# InputFilter.net
KiCad netlist of a schematic drawn in Altium Designer
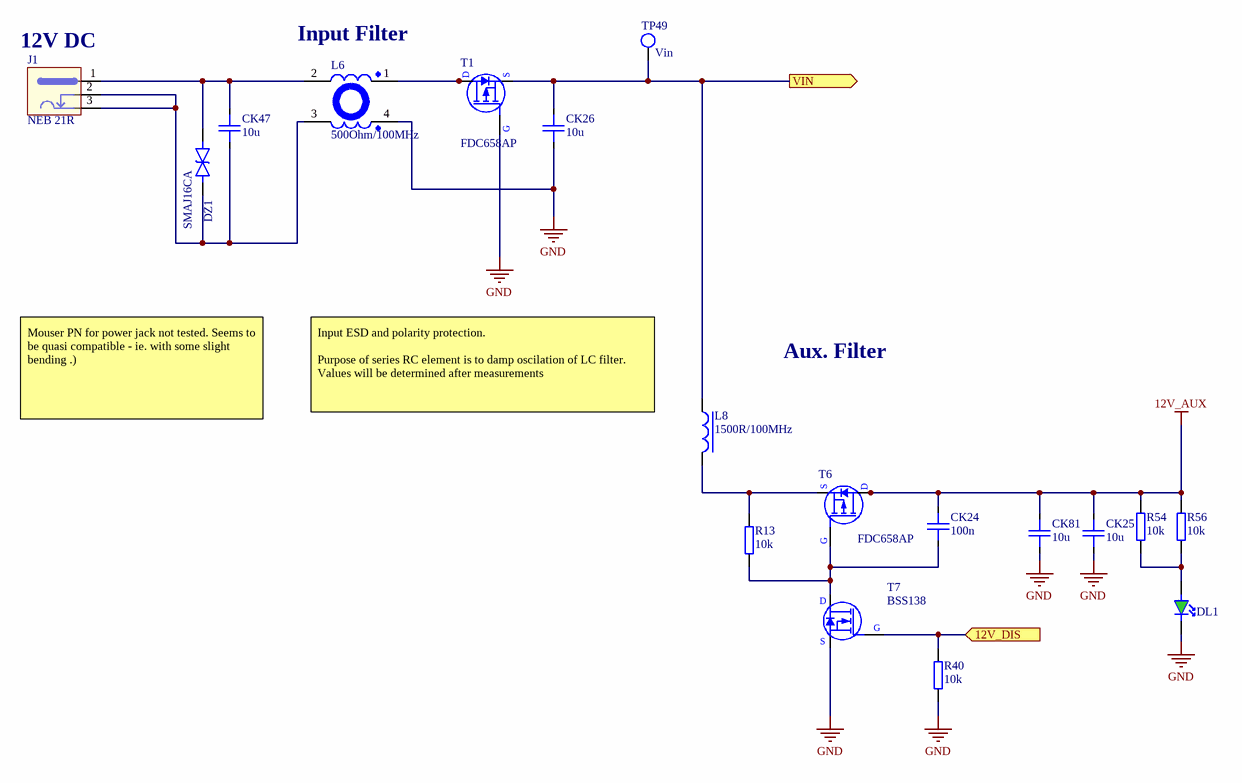
[diagram p0: InputFilter.SchDoc]

(export (version "E")
  (design (tool "Eeschema 10.0.6"))
  (components
    (comp (ref "CK24")
      (value "100n")
      (footprint "CAPC1608X09N(SMC0603)")
      (description "MLCC")
      (fields
        (field (name "TOLERANCE") "10%")
        (field (name "VOLTAGE") "50V")
        (field (name "AUTHOR") "JP/27.03.2014")
      )
      (libsource (lib "JP_C") (part "100n-50V-0603-X7R"))
    )
    (comp (ref "CK25")
      (value "10u")
      (footprint "CAPC3216X12N(SMC1206)")
      (description "MLCC")
      (fields
        (field (name "TOLERANCE") "10%")
        (field (name "VOLTAGE") "50")
        (field (name "AUTHOR") "JP/10.06.2014")
      )
      (libsource (lib "JP_C") (part "10u-50V-1206-X5R"))
    )
    (comp (ref "CK26")
      (value "10u")
      (footprint "CAPC3216X12N(SMC1206)")
      (description "MLCC")
      (fields
        (field (name "VOLTAGE") "50")
        (field (name "TOLERANCE") "10%")
        (field (name "AUTHOR") "JP/10.06.2014")
      )
      (libsource (lib "JP_C") (part "10u-50V-1206-X5R"))
    )
    (comp (ref "CK47")
      (value "10u")
      (footprint "CAPC3216X12N(SMC1206)")
      (description "MLCC")
      (fields
        (field (name "TOLERANCE") "10%")
        (field (name "VOLTAGE") "50")
        (field (name "AUTHOR") "JP/10.06.2014")
      )
      (libsource (lib "JP_C") (part "10u-50V-1206-X5R"))
    )
    (comp (ref "CK81")
      (value "10u")
      (footprint "CAPC3216X12N(SMC1206)")
      (description "MLCC")
      (fields
        (field (name "TOLERANCE") "10%")
        (field (name "VOLTAGE") "50")
        (field (name "AUTHOR") "JP/10.06.2014")
      )
      (libsource (lib "JP_C") (part "10u-50V-1206-X5R"))
    )
    (comp (ref "DL1")
      (value "GREEN")
      (footprint "0603diode")
      (description "Green LED, 0603")
      (fields (field (name "AUTHOR") "JP/31.3.2014"))
      (libsource (lib "IC") (part "LED_GREEN_0603"))
    )
    (comp (ref "DZ1")
      (value "SMAJ16CA")
      (footprint "DIOM5127X23N(SMA)")
      (description "Surface Mount TRANSZORB TVS, 16V StandOff, 400W, SMA")
      (libsource (lib "JP_IC") (part "SMAJ16CA"))
    )
    (comp (ref "J1")
      (value "NEB 21R")
      (footprint "NEB 21 R")
      (description "Power Jack Socket 1.95/6mm")
      (libsource (lib "JP_CONN") (part "Lumberg NEB 21 R"))
    )
    (comp (ref "L6")
      (value "500Ohm/100MHz")
      (footprint "DLW5BT")
      (description "CHOKE, COMMON, 4A, 500OHM, 100MHZ")
      (fields (field (name "AUTHOR") "JP 15.10.2014"))
      (libsource (lib "BTL_L") (part "EL+EMICHOKE4A"))
    )
    (comp (ref "L8")
      (value "1500R/100MHz")
      (footprint "INDC2012X08N(SML0805)")
      (description "Multilayer SMD Ferrite 1500R/100MHz")
      (fields (field (name "AUTHOR") "JP/05.06.2014"))
      (libsource (lib "JP_L") (part "MMZ2012Y152B"))
    )
    (comp (ref "R13")
      (value "10k")
      (footprint "RESC1608X06N(SMR0603)")
      (description "Chip Resistor")
      (fields (field (name "AUTHOR") "JP/10.06.2014"))
      (libsource (lib "JP_R") (part "10k-100mW-0603-ThickFilm"))
    )
    (comp (ref "R40")
      (value "10k")
      (footprint "RESC1608X06N(SMR0603)")
      (description "Chip Resistor")
      (fields (field (name "AUTHOR") "JP/10.06.2014"))
      (libsource (lib "JP_R") (part "10k-100mW-0603-ThickFilm"))
    )
    (comp (ref "R54")
      (value "10k")
      (footprint "RESC1608X06N(SMR0603)")
      (description "Chip Resistor")
      (fields (field (name "AUTHOR") "JP/10.06.2014"))
      (libsource (lib "JP_R") (part "10k-100mW-0603-ThickFilm"))
    )
    (comp (ref "R56")
      (value "10k")
      (footprint "RESC1608X06N(SMR0603)")
      (description "Chip Resistor")
      (fields (field (name "AUTHOR") "JP/10.06.2014"))
      (libsource (lib "JP_R") (part "10k-100mW-0603-ThickFilm"))
    )
    (comp (ref "T1")
      (value "FDC658AP")
      (footprint "TSOP95P280X110-6N(SuperSOT6)")
      (description "30V P  -  Channel PowerTrench  MOSFET")
      (libsource (lib "JP_IC") (part "FDC658AP"))
    )
    (comp (ref "T6")
      (value "FDC658AP")
      (footprint "TSOP95P280X110-6N(SuperSOT6)")
      (description "30V P  -  Channel PowerTrench  MOSFET")
      (libsource (lib "JP_IC") (part "FDC658AP"))
    )
    (comp (ref "T7")
      (value "BSS138")
      (footprint "SOT95P230X110-3N(SOT23)")
      (description "N-MOSFET, Logic Level, 50V/0,22A/3.5Ohm")
      (fields (field (name "AUTHOR") "JM 2.7.2014"))
      (libsource (lib "JP_IC") (part "ET+BSS138XX0"))
    )
    (comp (ref "TP49")
      (value "Vin")
      (footprint "TP_0.8/0.4_ROUND")
      (description "Testpoint - VIA")
      (libsource (lib "JP_CONN") (part "TEST_POINT_VIA"))
    )
  )
  (nets
    (net (code "1") (name "/12V_DIS") (class "Default")
      (node (ref "R40") (pin "2") (pinfunction "2_2") (pintype "passive"))
      (node (ref "T7") (pin "1") (pinfunction "G_1") (pintype "passive"))
    )
    (net (code "2") (name "/VIN") (class "Default")
      (node (ref "CK26") (pin "1") (pinfunction "1_1") (pintype "passive"))
      (node (ref "L8") (pin "1") (pintype "passive"))
      (node (ref "T1") (pin "4") (pinfunction "S_4") (pintype "passive"))
      (node (ref "TP49") (pin "1") (pintype "passive"))
    )
    (net (code "3") (name "12V_AUX") (class "Default")
      (node (ref "CK24") (pin "1") (pinfunction "1_1") (pintype "passive"))
      (node (ref "CK25") (pin "1") (pinfunction "1_1") (pintype "passive"))
      (node (ref "CK81") (pin "1") (pinfunction "1_1") (pintype "passive"))
      (node (ref "R54") (pin "2") (pinfunction "2_2") (pintype "passive"))
      (node (ref "R56") (pin "2") (pinfunction "2_2") (pintype "passive"))
      (node (ref "T6") (pin "1") (pinfunction "D_1") (pintype "passive"))
      (node (ref "T6") (pin "2") (pinfunction "D_2") (pintype "passive"))
      (node (ref "T6") (pin "5") (pinfunction "D_5") (pintype "passive"))
      (node (ref "T6") (pin "6") (pinfunction "D_6") (pintype "passive"))
    )
    (net (code "4") (name "GND") (class "Default")
      (node (ref "CK25") (pin "2") (pinfunction "2_2") (pintype "passive"))
      (node (ref "CK26") (pin "2") (pinfunction "2_2") (pintype "passive"))
      (node (ref "CK81") (pin "2") (pinfunction "2_2") (pintype "passive"))
      (node (ref "DL1") (pin "1") (pinfunction "C_1") (pintype "passive"))
      (node (ref "L6") (pin "4") (pintype "passive"))
      (node (ref "R40") (pin "1") (pinfunction "1_1") (pintype "passive"))
      (node (ref "T1") (pin "3") (pinfunction "G_3") (pintype "passive"))
      (node (ref "T7") (pin "2") (pinfunction "S_2") (pintype "passive"))
    )
    (net (code "5") (name "Net-(CK47-Pad2)") (class "Default")
      (node (ref "CK47") (pin "2") (pinfunction "2_2") (pintype "passive"))
      (node (ref "DZ1") (pin "2") (pinfunction "AC_2") (pintype "passive"))
      (node (ref "J1") (pin "2") (pinfunction "GND_2") (pintype "passive"))
      (node (ref "J1") (pin "3") (pinfunction "GND_3") (pintype "passive"))
      (node (ref "L6") (pin "3") (pintype "passive"))
    )
    (net (code "6") (name "Net-(DL1-A)") (class "Default")
      (node (ref "DL1") (pin "2") (pinfunction "A_2") (pintype "passive"))
      (node (ref "R54") (pin "1") (pinfunction "1_1") (pintype "passive"))
      (node (ref "R56") (pin "1") (pinfunction "1_1") (pintype "passive"))
    )
    (net (code "7") (name "Net-(J1-Signal)") (class "Default")
      (node (ref "CK47") (pin "1") (pinfunction "1_1") (pintype "passive"))
      (node (ref "DZ1") (pin "1") (pinfunction "AC_1") (pintype "passive"))
      (node (ref "J1") (pin "1") (pinfunction "Signal_1") (pintype "passive"))
      (node (ref "L6") (pin "2") (pintype "passive"))
    )
    (net (code "8") (name "Net-(L6-Pad1)") (class "Default")
      (node (ref "L6") (pin "1") (pintype "passive"))
      (node (ref "T1") (pin "1") (pinfunction "D_1") (pintype "passive"))
      (node (ref "T1") (pin "2") (pinfunction "D_2") (pintype "passive"))
      (node (ref "T1") (pin "5") (pinfunction "D_5") (pintype "passive"))
      (node (ref "T1") (pin "6") (pinfunction "D_6") (pintype "passive"))
    )
    (net (code "9") (name "Net-(T6-G)") (class "Default")
      (node (ref "CK24") (pin "2") (pinfunction "2_2") (pintype "passive"))
      (node (ref "R13") (pin "1") (pinfunction "1_1") (pintype "passive"))
      (node (ref "T6") (pin "3") (pinfunction "G_3") (pintype "passive"))
      (node (ref "T7") (pin "3") (pinfunction "D_3") (pintype "passive"))
    )
    (net (code "10") (name "Net-(T6-S)") (class "Default")
      (node (ref "L8") (pin "2") (pintype "passive"))
      (node (ref "R13") (pin "2") (pinfunction "2_2") (pintype "passive"))
      (node (ref "T6") (pin "4") (pinfunction "S_4") (pintype "passive"))
    )
  )
)
